# FT4222_Schematic.net
KiCad netlist of a schematic drawn in Altium Designer
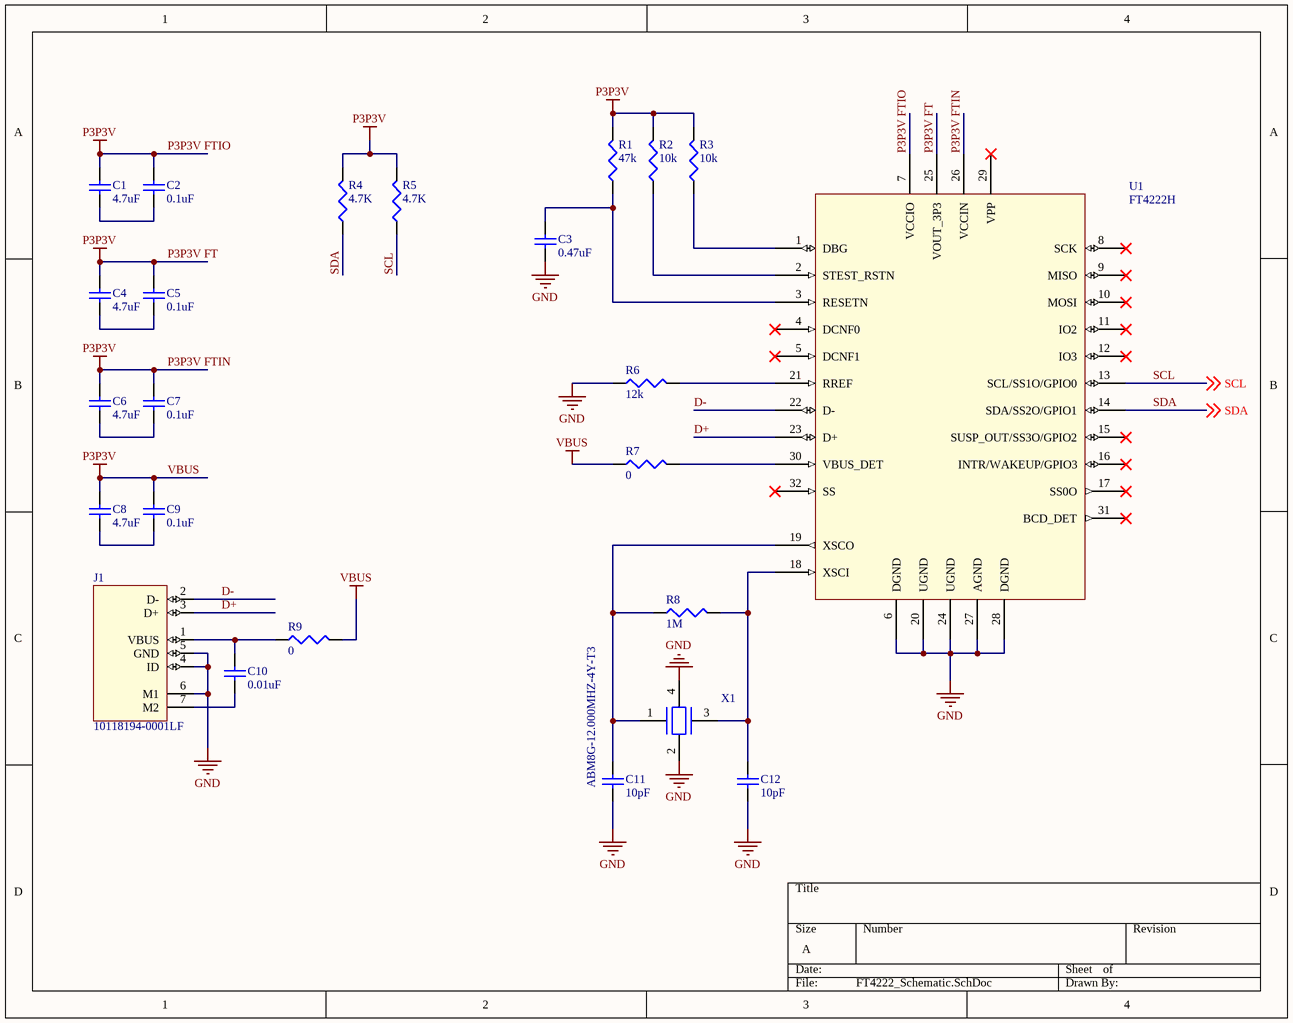
[diagram p0: FT4222_Schematic.SchDoc]

(export (version "E")
  (design (tool "Eeschema 10.0.6"))
  (components
    (comp (ref "C1")
      (value "4.7uF")
      (footprint "CAP_0402_MED")
      (description "CAP CER 4.7UF 16V X5R 0402")
      (fields (field (name "MFGPARTNO") "0402YD475MAT2A") (field (name "MFG") "AVX"))
      (libsource (lib "SLA3000-FPGA[4086]") (part "CMP-00798-A.1"))
    )
    (comp (ref "C2")
      (value "0.1uF")
      (footprint "CAP_0402_MED")
      (description "CAP CER 0.1UF 25V X7R 0402")
      (fields (field (name "SLA PART NO") "SL00150") (field (name "MFG") "TDK"))
      (libsource (lib "SLA3000-FPGA[4086]") (part "CMP-00496-A.6"))
    )
    (comp (ref "C3")
      (value "0.47uF")
      (footprint "CAP_0603_MED")
      (description "CAP CER 0.47UF 16V 10% X7R 0603")
      (fields (field (name "SLA PART NO") "SL00008") (field (name "MFG") "Kemet"))
      (libsource (lib "SLA3000-FPGA[4086]") (part "CMP-00498-A.6"))
    )
    (comp (ref "C4")
      (value "4.7uF")
      (footprint "CAP_0402_MED")
      (description "CAP CER 4.7UF 16V X5R 0402")
      (fields (field (name "MFGPARTNO") "0402YD475MAT2A") (field (name "MFG") "AVX"))
      (libsource (lib "SLA3000-FPGA[4086]") (part "CMP-00798-A.1"))
    )
    (comp (ref "C5")
      (value "0.1uF")
      (footprint "CAP_0402_MED")
      (description "CAP CER 0.1UF 25V X7R 0402")
      (fields (field (name "SLA PART NO") "SL00150") (field (name "MFG") "TDK"))
      (libsource (lib "SLA3000-FPGA[4086]") (part "CMP-00496-A.6"))
    )
    (comp (ref "C6")
      (value "4.7uF")
      (footprint "CAP_0402_MED")
      (description "CAP CER 4.7UF 16V X5R 0402")
      (fields (field (name "MFGPARTNO") "0402YD475MAT2A") (field (name "MFG") "AVX"))
      (libsource (lib "SLA3000-FPGA[4086]") (part "CMP-00798-A.1"))
    )
    (comp (ref "C7")
      (value "0.1uF")
      (footprint "CAP_0402_MED")
      (description "CAP CER 0.1UF 25V X7R 0402")
      (fields (field (name "SLA PART NO") "SL00150") (field (name "MFG") "TDK"))
      (libsource (lib "SLA3000-FPGA[4086]") (part "CMP-00496-A.6"))
    )
    (comp (ref "C8")
      (value "4.7uF")
      (footprint "CAP_0402_MED")
      (description "CAP CER 4.7UF 16V X5R 0402")
      (fields (field (name "MFGPARTNO") "0402YD475MAT2A") (field (name "MFG") "AVX"))
      (libsource (lib "SLA3000-FPGA[4086]") (part "CMP-00798-A.1"))
    )
    (comp (ref "C9")
      (value "0.1uF")
      (footprint "CAP_0402_MED")
      (description "CAP CER 0.1UF 25V X7R 0402")
      (fields (field (name "SLA PART NO") "SL00150") (field (name "MFG") "TDK"))
      (libsource (lib "SLA3000-FPGA[4086]") (part "CMP-00496-A.6"))
    )
    (comp (ref "C10")
      (value "0.01uF")
      (footprint "CAP_0402_MED")
      (description "CAP CER 0.1UF 25V X7R 0402")
      (fields (field (name "SLA PART NO") "SL00150") (field (name "MFG") "TDK"))
      (libsource (lib "SLA3000-FPGA[4086]") (part "CMP-00496-A.6"))
    )
    (comp (ref "C11")
      (value "10pF")
      (footprint "CAP_0402_MED")
      (description "CAP CER 10PF 50V C0G/NP0 0402")
      (fields (field (name "MFGPARTNO") "GCM1555C1H100FA16D") (field (name "MFG") "Murata"))
      (libsource (lib "SLA3000-FPGA[4086]") (part "CMP-00614-A.1"))
    )
    (comp (ref "C12")
      (value "10pF")
      (footprint "CAP_0402_MED")
      (description "CAP CER 10PF 50V C0G/NP0 0402")
      (fields (field (name "MFGPARTNO") "GCM1555C1H100FA16D") (field (name "MFG") "Murata"))
      (libsource (lib "SLA3000-FPGA[4086]") (part "CMP-00614-A.1"))
    )
    (comp (ref "J1")
      (value "10118194-0001LF")
      (footprint "10118194-0001LF")
      (description "10118194-0001LF CONN USB MICRO B RECPT THRU-SMT R/A")
      (fields (field (name "MFG") "Amphenol"))
      (libsource (lib "SLA3000-FPGA[4086]") (part "CMP-00755-A.2"))
    )
    (comp (ref "R1")
      (value "47k")
      (footprint "RES_0402_MED")
      (description "RES SMD 47K OHM 1% 1/10W 0402")
      (fields (field (name "MFG") "Panasonic") (field (name "MFGPARTNO") "ERJ-U02F4702X"))
      (libsource (lib "SLA3000-FPGA[4086]") (part "CMP-00852-A.2"))
    )
    (comp (ref "R2")
      (value "10k")
      (footprint "RES_0402_MED")
      (description "RES SMD 10K OHM 1% 1/10W 0402")
      (fields (field (name "SLA PART NO") "SL00225") (field (name "MFG") "Panasonic"))
      (libsource (lib "SLA3000-FPGA[4086]") (part "CMP-00396-A.9"))
    )
    (comp (ref "R3")
      (value "10k")
      (footprint "RES_0402_MED")
      (description "RES SMD 10K OHM 1% 1/10W 0402")
      (fields (field (name "SLA PART NO") "SL00225") (field (name "MFG") "Panasonic"))
      (libsource (lib "SLA3000-FPGA[4086]") (part "CMP-00396-A.9"))
    )
    (comp (ref "R4")
      (value "4.7K")
      (footprint "RES_0402_MED")
      (description "RES SMD 4K7 OHM 1% 1/16W 0402")
      (fields (field (name "MFGPARTNO") "RC0402FR-074K7P") (field (name "MFG") "Yageo"))
      (libsource (lib "SLA3000-FPGA[4086]") (part "CMP-00761-A.1"))
    )
    (comp (ref "R5")
      (value "4.7K")
      (footprint "RES_0402_MED")
      (description "RES SMD 4K7 OHM 1% 1/16W 0402")
      (fields (field (name "MFGPARTNO") "RC0402FR-074K7P") (field (name "MFG") "Yageo"))
      (libsource (lib "SLA3000-FPGA[4086]") (part "CMP-00761-A.1"))
    )
    (comp (ref "R6")
      (value "12k")
      (footprint "RES_0402_MED")
      (description "RES SMD 12K OHM 1% 1/16W 0402")
      (fields (field (name "MFG") "Yageo") (field (name "MFGPARTNO") "RC0402FR-0712KL"))
      (libsource (lib "SLA3000-FPGA[4086]") (part "CMP-00612-A.1"))
    )
    (comp (ref "R7")
      (value "0")
      (footprint "RES_0603_MED")
      (description "RES SMD 0.0OHM JUMPER 1/10W 0603")
      (fields (field (name "MFG") "Panasonic") (field (name "MFGPARTNO") "ERJ-3GEY0R00V"))
      (libsource (lib "SLA3000-FPGA[4086]") (part "CMP-00342-A.7"))
    )
    (comp (ref "R8")
      (value "1M")
      (footprint "RES_0402_MED")
      (description "RES SMD 1M OHM 1% 1/10W 0402")
      (fields (field (name "MFGPARTNO") "ERJ-2RKF1004X") (field (name "SLA PART NO") "SL00141"))
      (libsource (lib "SLA3000-FPGA[4086]") (part "CMP-00430-A.9"))
    )
    (comp (ref "R9")
      (value "0")
      (footprint "RES_0402_MED")
      (description "RES SMD 0.0OHM JUMPER 1/10W 0402")
      (fields (field (name "SLA PART NO") "SL00128") (field (name "MFGPARTNO") "ERJ-2GE0R00X"))
      (libsource (lib "SLA3000-FPGA[4086]") (part "CMP-00341-A.9"))
    )
    (comp (ref "U1")
      (value "FT4222H")
      (footprint "VQFN-32")
      (description "FT4222H USB2.0 TO QUADSPI/I2C BRIDGE IC VQFN-32")
      (fields (field (name "MFG") "FTDI"))
      (libsource (lib "SLA3000-FPGA[4086]") (part "CMP-00851-A.3"))
    )
    (comp (ref "X1")
      (value "ABM8G-12.000MHZ-4Y-T3")
      (footprint "ABM8G")
      (description "CRYSTAL 12.0000MHZ 10PF SMD")
      (fields (field (name "MFG") "Abracon"))
      (libsource (lib "SLA3000-FPGA[4086]") (part "CMP-00613-A.2"))
    )
  )
  (nets
    (net (code "1") (name "/D+") (class "Default")
      (node (ref "J1") (pin "3") (pinfunction "D+_3") (pintype "bidirectional"))
      (node (ref "U1") (pin "23") (pinfunction "D+_23") (pintype "bidirectional"))
    )
    (net (code "2") (name "/D-") (class "Default")
      (node (ref "J1") (pin "2") (pinfunction "D-_2") (pintype "bidirectional"))
      (node (ref "U1") (pin "22") (pinfunction "D-_22") (pintype "bidirectional"))
    )
    (net (code "3") (name "GND") (class "Default")
      (node (ref "C11") (pin "1") (pinfunction "1_1") (pintype "passive"))
      (node (ref "C12") (pin "1") (pinfunction "1_1") (pintype "passive"))
      (node (ref "C3") (pin "1") (pinfunction "1_1") (pintype "passive"))
      (node (ref "J1") (pin "4") (pinfunction "ID_4") (pintype "bidirectional"))
      (node (ref "J1") (pin "5") (pinfunction "GND_5") (pintype "bidirectional"))
      (node (ref "J1") (pin "6") (pinfunction "M1_6") (pintype "passive"))
      (node (ref "R6") (pin "1") (pinfunction "1_1") (pintype "passive"))
      (node (ref "U1") (pin "20") (pinfunction "UGND_20") (pintype "power_in"))
      (node (ref "U1") (pin "24") (pinfunction "UGND_24") (pintype "power_in"))
      (node (ref "U1") (pin "27") (pinfunction "AGND_27") (pintype "power_in"))
      (node (ref "U1") (pin "28") (pinfunction "DGND_28") (pintype "power_in"))
      (node (ref "U1") (pin "6") (pinfunction "DGND_6") (pintype "power_in"))
      (node (ref "X1") (pin "2") (pinfunction "GND_2") (pintype "power_in"))
      (node (ref "X1") (pin "4") (pinfunction "GND_4") (pintype "power_in"))
    )
    (net (code "4") (name "Net-(C1-Pad1)") (class "Default")
      (node (ref "C1") (pin "1") (pinfunction "1_1") (pintype "passive"))
      (node (ref "C2") (pin "1") (pinfunction "1_1") (pintype "passive"))
    )
    (net (code "5") (name "Net-(C4-Pad1)") (class "Default")
      (node (ref "C4") (pin "1") (pinfunction "1_1") (pintype "passive"))
      (node (ref "C5") (pin "1") (pinfunction "1_1") (pintype "passive"))
    )
    (net (code "6") (name "Net-(C6-Pad1)") (class "Default")
      (node (ref "C6") (pin "1") (pinfunction "1_1") (pintype "passive"))
      (node (ref "C7") (pin "1") (pinfunction "1_1") (pintype "passive"))
    )
    (net (code "7") (name "Net-(C8-Pad1)") (class "Default")
      (node (ref "C8") (pin "1") (pinfunction "1_1") (pintype "passive"))
      (node (ref "C9") (pin "1") (pinfunction "1_1") (pintype "passive"))
    )
    (net (code "8") (name "Net-(J1-M2)") (class "Default")
      (node (ref "C10") (pin "1") (pinfunction "1_1") (pintype "passive"))
      (node (ref "J1") (pin "7") (pinfunction "M2_7") (pintype "passive"))
    )
    (net (code "9") (name "Net-(J1-VBUS)") (class "Default")
      (node (ref "C10") (pin "2") (pinfunction "2_2") (pintype "passive"))
      (node (ref "J1") (pin "1") (pinfunction "VBUS_1") (pintype "bidirectional"))
      (node (ref "R9") (pin "1") (pinfunction "1_1") (pintype "passive"))
    )
    (net (code "10") (name "Net-(U1-DBG)") (class "Default")
      (node (ref "R3") (pin "1") (pinfunction "1_1") (pintype "passive"))
      (node (ref "U1") (pin "1") (pinfunction "DBG_1") (pintype "bidirectional"))
    )
    (net (code "11") (name "Net-(U1-RESETN)") (class "Default")
      (node (ref "C3") (pin "2") (pinfunction "2_2") (pintype "passive"))
      (node (ref "R1") (pin "1") (pinfunction "1_1") (pintype "passive"))
      (node (ref "U1") (pin "3") (pinfunction "RESETN_3") (pintype "input"))
    )
    (net (code "12") (name "Net-(U1-RREF)") (class "Default")
      (node (ref "R6") (pin "2") (pinfunction "2_2") (pintype "passive"))
      (node (ref "U1") (pin "21") (pinfunction "RREF_21") (pintype "input"))
    )
    (net (code "13") (name "Net-(U1-STEST_RSTN)") (class "Default")
      (node (ref "R2") (pin "1") (pinfunction "1_1") (pintype "passive"))
      (node (ref "U1") (pin "2") (pinfunction "STEST_RSTN_2") (pintype "input"))
    )
    (net (code "14") (name "Net-(U1-VBUS_DET)") (class "Default")
      (node (ref "R7") (pin "2") (pinfunction "2_2") (pintype "passive"))
      (node (ref "U1") (pin "30") (pinfunction "VBUS_DET_30") (pintype "input"))
    )
    (net (code "15") (name "Net-(U1-XSCI)") (class "Default")
      (node (ref "C12") (pin "2") (pinfunction "2_2") (pintype "passive"))
      (node (ref "R8") (pin "2") (pinfunction "2_2") (pintype "passive"))
      (node (ref "U1") (pin "18") (pinfunction "XSCI_18") (pintype "input"))
      (node (ref "X1") (pin "3") (pinfunction "OSC2_3") (pintype "passive"))
    )
    (net (code "16") (name "Net-(U1-XSCO)") (class "Default")
      (node (ref "C11") (pin "2") (pinfunction "2_2") (pintype "passive"))
      (node (ref "R8") (pin "1") (pinfunction "1_1") (pintype "passive"))
      (node (ref "U1") (pin "19") (pinfunction "XSCO_19") (pintype "output"))
      (node (ref "X1") (pin "1") (pinfunction "OSC1_1") (pintype "passive"))
    )
    (net (code "17") (name "P3P3V") (class "Default")
      (node (ref "C1") (pin "2") (pinfunction "2_2") (pintype "passive"))
      (node (ref "C2") (pin "2") (pinfunction "2_2") (pintype "passive"))
      (node (ref "C4") (pin "2") (pinfunction "2_2") (pintype "passive"))
      (node (ref "C5") (pin "2") (pinfunction "2_2") (pintype "passive"))
      (node (ref "C6") (pin "2") (pinfunction "2_2") (pintype "passive"))
      (node (ref "C7") (pin "2") (pinfunction "2_2") (pintype "passive"))
      (node (ref "C8") (pin "2") (pinfunction "2_2") (pintype "passive"))
      (node (ref "C9") (pin "2") (pinfunction "2_2") (pintype "passive"))
      (node (ref "R1") (pin "2") (pinfunction "2_2") (pintype "passive"))
      (node (ref "R2") (pin "2") (pinfunction "2_2") (pintype "passive"))
      (node (ref "R3") (pin "2") (pinfunction "2_2") (pintype "passive"))
      (node (ref "R4") (pin "2") (pinfunction "2_2") (pintype "passive"))
      (node (ref "R5") (pin "2") (pinfunction "2_2") (pintype "passive"))
      (node (ref "R7") (pin "1") (pinfunction "1_1") (pintype "passive"))
      (node (ref "R9") (pin "2") (pinfunction "2_2") (pintype "passive"))
      (node (ref "U1") (pin "25") (pinfunction "VOUT_3P3_25") (pintype "power_in"))
      (node (ref "U1") (pin "26") (pinfunction "VCCIN_26") (pintype "power_in"))
      (node (ref "U1") (pin "7") (pinfunction "VCCIO_7") (pintype "power_in"))
    )
    (net (code "18") (name "SCL") (class "Default")
      (node (ref "R5") (pin "1") (pinfunction "1_1") (pintype "passive"))
      (node (ref "U1") (pin "13") (pinfunction "SCL/SS1O/GPIO0_13") (pintype "bidirectional"))
    )
    (net (code "19") (name "SDA") (class "Default")
      (node (ref "R4") (pin "1") (pinfunction "1_1") (pintype "passive"))
      (node (ref "U1") (pin "14") (pinfunction "SDA/SS2O/GPIO1_14") (pintype "bidirectional"))
    )
    (net (code "20") (name "unconnected-(U1-BCD_DET-Pad31)") (class "Default")
      (node (ref "U1") (pin "31") (pinfunction "BCD_DET_31") (pintype "output+no_connect"))
    )
    (net (code "21") (name "unconnected-(U1-DCNF0-Pad4)") (class "Default")
      (node (ref "U1") (pin "4") (pinfunction "DCNF0_4") (pintype "input+no_connect"))
    )
    (net (code "22") (name "unconnected-(U1-DCNF1-Pad5)") (class "Default")
      (node (ref "U1") (pin "5") (pinfunction "DCNF1_5") (pintype "input+no_connect"))
    )
    (net (code "23") (name "unconnected-(U1-INTR{slash}WAKEUP{slash}GPIO3-Pad16)") (class "Default")
      (node (ref "U1") (pin "16") (pinfunction "INTR/WAKEUP/GPIO3_16") (pintype "bidirectional+no_connect"))
    )
    (net (code "24") (name "unconnected-(U1-IO2-Pad11)") (class "Default")
      (node (ref "U1") (pin "11") (pinfunction "IO2_11") (pintype "bidirectional+no_connect"))
    )
    (net (code "25") (name "unconnected-(U1-IO3-Pad12)") (class "Default")
      (node (ref "U1") (pin "12") (pinfunction "IO3_12") (pintype "bidirectional+no_connect"))
    )
    (net (code "26") (name "unconnected-(U1-MISO-Pad9)") (class "Default")
      (node (ref "U1") (pin "9") (pinfunction "MISO_9") (pintype "bidirectional+no_connect"))
    )
    (net (code "27") (name "unconnected-(U1-MOSI-Pad10)") (class "Default")
      (node (ref "U1") (pin "10") (pinfunction "MOSI_10") (pintype "bidirectional+no_connect"))
    )
    (net (code "28") (name "unconnected-(U1-SCK-Pad8)") (class "Default")
      (node (ref "U1") (pin "8") (pinfunction "SCK_8") (pintype "bidirectional+no_connect"))
    )
    (net (code "29") (name "unconnected-(U1-SS-Pad32)") (class "Default")
      (node (ref "U1") (pin "32") (pinfunction "SS_32") (pintype "input+no_connect"))
    )
    (net (code "30") (name "unconnected-(U1-SS0O-Pad17)") (class "Default")
      (node (ref "U1") (pin "17") (pinfunction "SS0O_17") (pintype "output+no_connect"))
    )
    (net (code "31") (name "unconnected-(U1-SUSP_OUT{slash}SS3O{slash}GPIO2-Pad15)") (class "Default")
      (node (ref "U1") (pin "15") (pinfunction "SUSP_OUT/SS3O/GPIO2_15") (pintype "bidirectional+no_connect"))
    )
    (net (code "32") (name "unconnected-(U1-VPP-Pad29)") (class "Default")
      (node (ref "U1") (pin "29") (pinfunction "VPP_29") (pintype "power_in+no_connect"))
    )
  )
)
